# main.net
KiCad netlist of a schematic drawn in Altium Designer
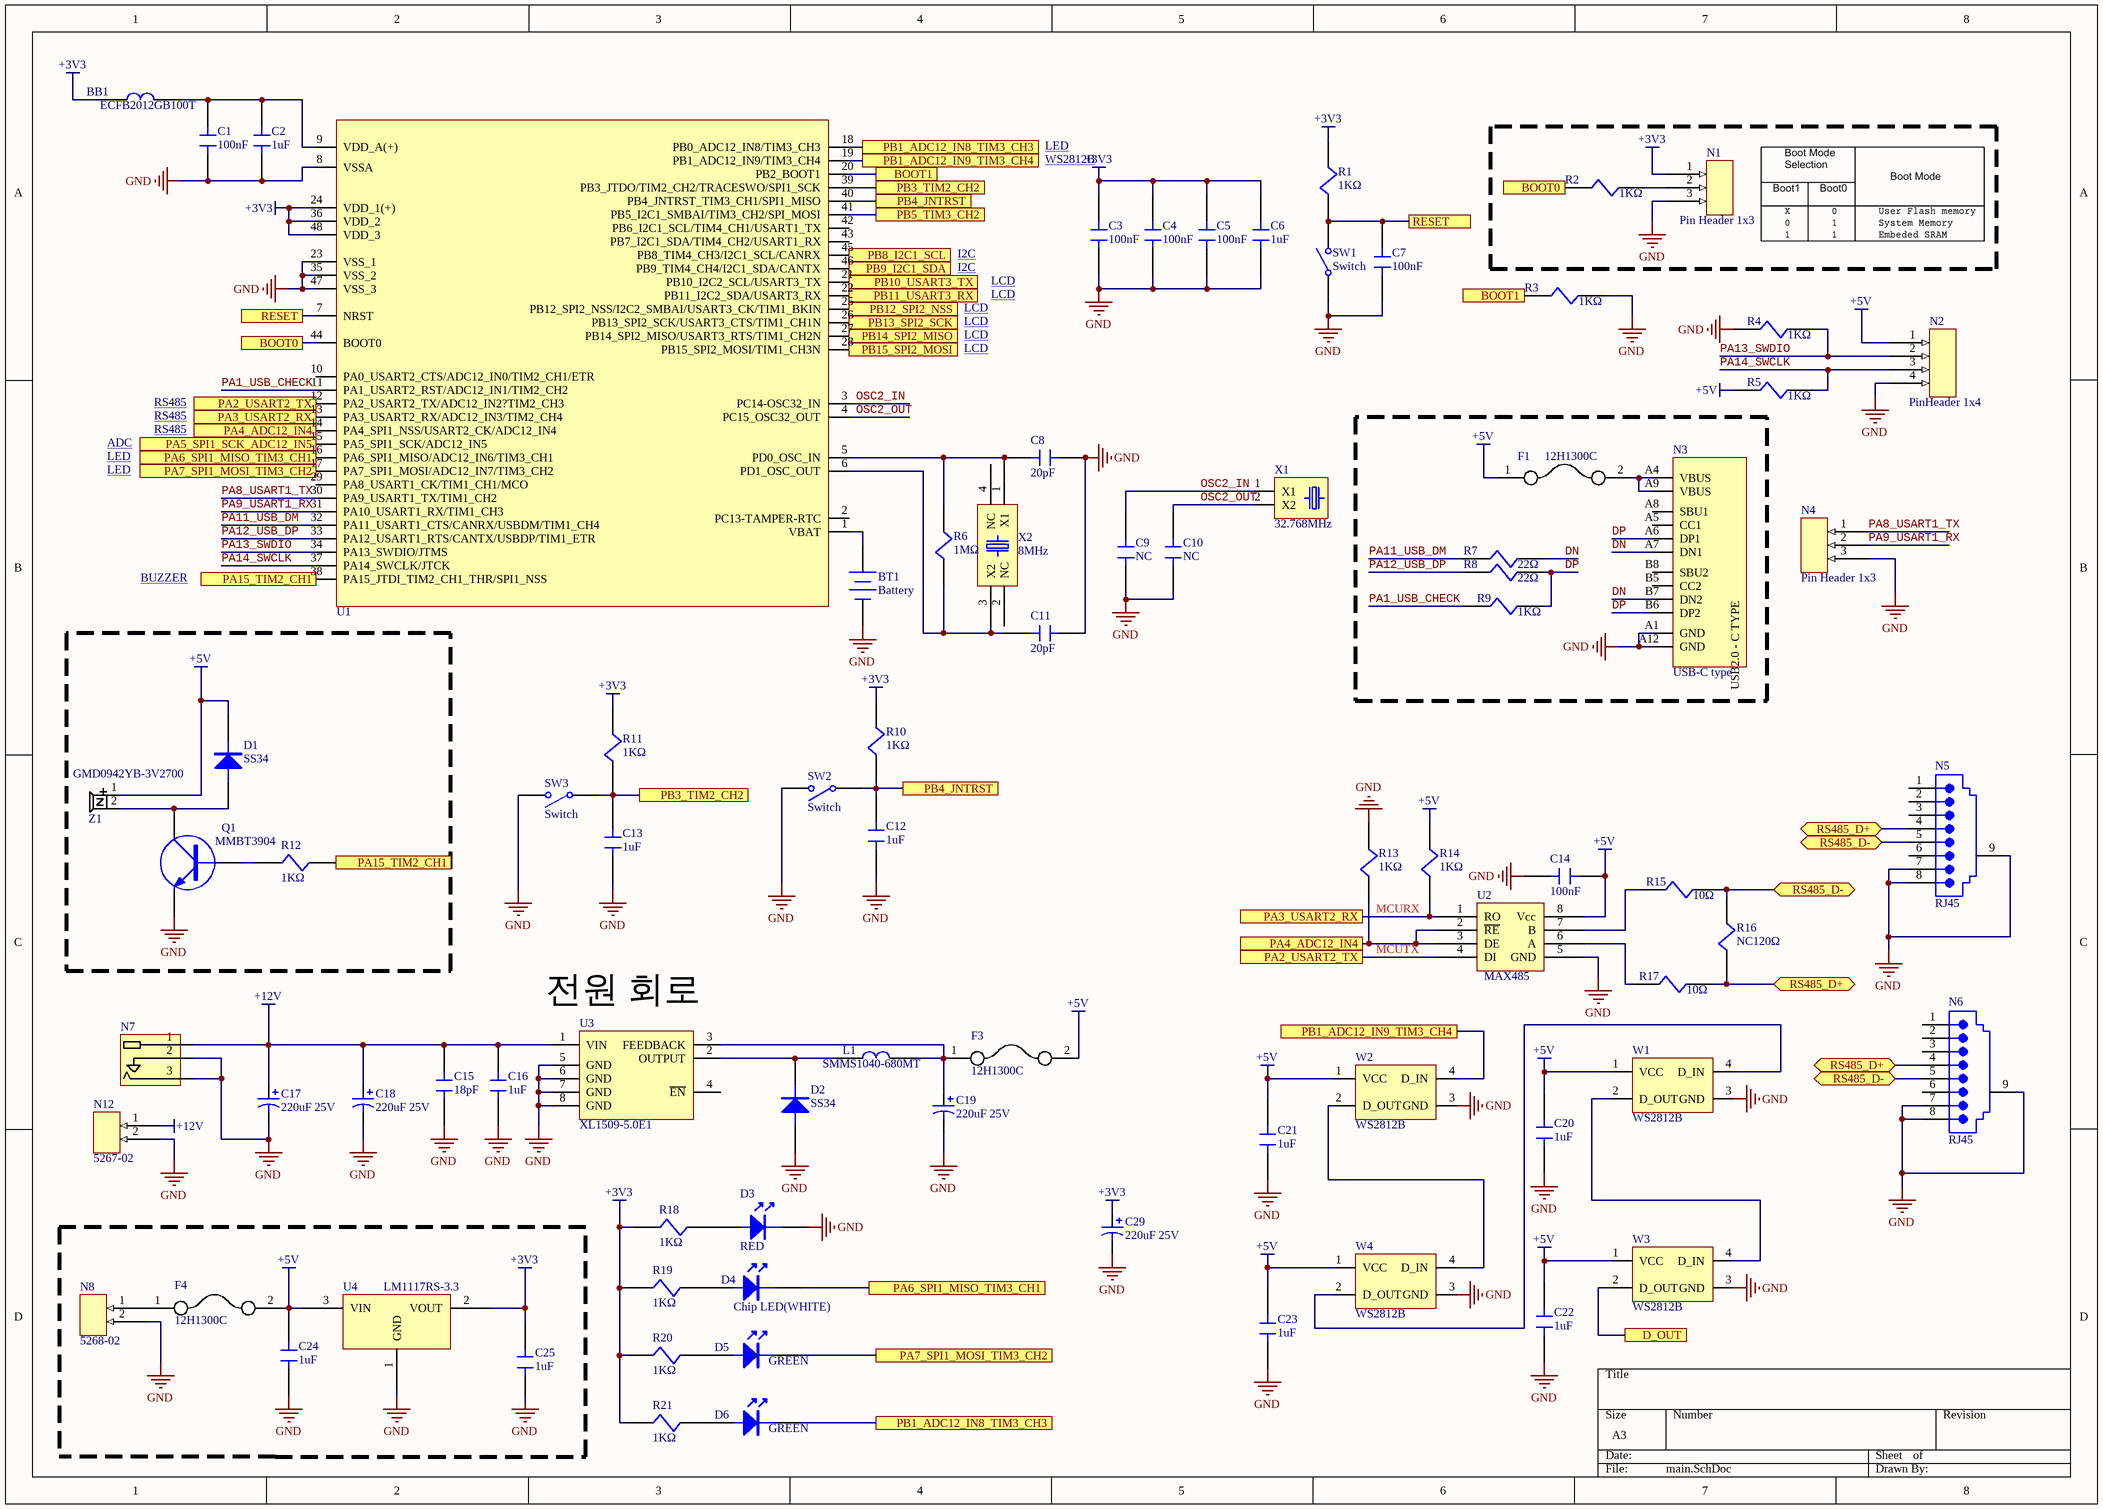
[diagram p0: main.SchDoc]

(export (version "E")
  (design (tool "Eeschema 10.0.6"))
  (components
    (comp (ref "BB1")
      (value "BEAD")
      (footprint "2012-L")
      (description "2012 type Bead")
      (fields (field (name "PART NUMBER") "ECFB2012GB100T"))
      (libsource (lib "SCH_LIB") (part "IND1"))
    )
    (comp (ref "BT1")
      (value "Battery")
      (footprint "CR2032_SMD")
      (description "Multicell Battery")
      (fields (field (name "PUBLISHER") "Altium Limited"))
      (libsource (lib "Miscellaneous Devices") (part "Battery"))
    )
    (comp (ref "C1")
      (value "Chip Capacitor")
      (footprint "1608-C")
      (description "Capacitor, 1608 type")
      (fields (field (name "PART NUMBER") "100nF"))
      (libsource (lib "*") (part "CAP"))
    )
    (comp (ref "C2")
      (value "Chip Capacitor")
      (footprint "1608-C")
      (description "Capacitor, 1608 type")
      (fields (field (name "PART NUMBER") "1uF"))
      (libsource (lib "*") (part "CAP"))
    )
    (comp (ref "C3")
      (value "Chip Capacitor")
      (footprint "1608-C")
      (description "Capacitor, 1608 type")
      (fields (field (name "PART NUMBER") "100nF"))
      (libsource (lib "*") (part "CAP"))
    )
    (comp (ref "C4")
      (value "Chip Capacitor")
      (footprint "1608-C")
      (description "Capacitor, 1608 type")
      (fields (field (name "PART NUMBER") "100nF"))
      (libsource (lib "*") (part "CAP"))
    )
    (comp (ref "C5")
      (value "Chip Capacitor")
      (footprint "1608-C")
      (description "Capacitor, 1608 type")
      (fields (field (name "PART NUMBER") "100nF"))
      (libsource (lib "*") (part "CAP"))
    )
    (comp (ref "C6")
      (value "Chip Capacitor")
      (footprint "1608-C")
      (description "Capacitor, 1608 type")
      (fields (field (name "PART NUMBER") "1uF"))
      (libsource (lib "*") (part "CAP"))
    )
    (comp (ref "C7")
      (value "Chip Capacitor")
      (footprint "1608-C")
      (description "Capacitor, 1608 type")
      (fields (field (name "PART NUMBER") "100nF"))
      (libsource (lib "*") (part "CAP"))
    )
    (comp (ref "C8")
      (value "Chip Capacitor")
      (footprint "1608-C")
      (description "Capacitor, 1608 type")
      (fields (field (name "PART NUMBER") "20pF"))
      (libsource (lib "*") (part "CAP"))
    )
    (comp (ref "C9")
      (value "Chip Capacitor")
      (footprint "1608-C")
      (description "Capacitor, 1608 type")
      (fields (field (name "PART NUMBER") "NC"))
      (libsource (lib "*") (part "CAP"))
    )
    (comp (ref "C10")
      (value "Chip Capacitor")
      (footprint "1608-C")
      (description "Capacitor, 1608 type")
      (fields (field (name "PART NUMBER") "NC"))
      (libsource (lib "*") (part "CAP"))
    )
    (comp (ref "C11")
      (value "Chip Capacitor")
      (footprint "1608-C")
      (description "Capacitor, 1608 type")
      (fields (field (name "PART NUMBER") "20pF"))
      (libsource (lib "*") (part "CAP"))
    )
    (comp (ref "C12")
      (value "Chip Capacitor")
      (footprint "1608-C")
      (description "Capacitor, 1608 type")
      (fields (field (name "PART NUMBER") "1uF"))
      (libsource (lib "*") (part "CAP"))
    )
    (comp (ref "C13")
      (value "Chip Capacitor")
      (footprint "1608-C")
      (description "Capacitor, 1608 type")
      (fields (field (name "PART NUMBER") "1uF"))
      (libsource (lib "*") (part "CAP"))
    )
    (comp (ref "C14")
      (value "Chip Capacitor")
      (footprint "1608-C")
      (description "Capacitor, 1608 type")
      (fields (field (name "PART NUMBER") "100nF"))
      (libsource (lib "*") (part "CAP"))
    )
    (comp (ref "C15")
      (value "Chip Capacitor")
      (footprint "1608-C")
      (description "Capacitor, 1608 type")
      (fields (field (name "PART NUMBER") "18pF"))
      (libsource (lib "*") (part "CAP"))
    )
    (comp (ref "C16")
      (value "Chip Capacitor")
      (footprint "1608-C")
      (description "Capacitor, 1608 type")
      (fields (field (name "PART NUMBER") "1uF"))
      (libsource (lib "*") (part "CAP"))
    )
    (comp (ref "C17")
      (value "Capacitor")
      (footprint "CAP_8X10")
      (description "TanTal Capacitor")
      (fields (field (name "PART NUMBER") "220uF 25V"))
      (libsource (lib "Miscellaneous Devices") (part "Cap Pol1"))
    )
    (comp (ref "C18")
      (value "Capacitor")
      (footprint "CAP_8X10")
      (description "TanTal Capacitor")
      (fields (field (name "PART NUMBER") "220uF 25V"))
      (libsource (lib "Miscellaneous Devices") (part "Cap Pol1"))
    )
    (comp (ref "C19")
      (value "Capacitor")
      (footprint "CAP_8X10")
      (description "TanTal Capacitor")
      (fields (field (name "PART NUMBER") "220uF 25V"))
      (libsource (lib "Miscellaneous Devices") (part "Cap Pol1"))
    )
    (comp (ref "C20")
      (value "Chip Capacitor")
      (footprint "1608-C")
      (description "Capacitor, 1608 type")
      (fields (field (name "PART NUMBER") "1uF"))
      (libsource (lib "*") (part "CAP"))
    )
    (comp (ref "C21")
      (value "Chip Capacitor")
      (footprint "1608-C")
      (description "Capacitor, 1608 type")
      (fields (field (name "PART NUMBER") "1uF"))
      (libsource (lib "*") (part "CAP"))
    )
    (comp (ref "C22")
      (value "Chip Capacitor")
      (footprint "1608-C")
      (description "Capacitor, 1608 type")
      (fields (field (name "PART NUMBER") "1uF"))
      (libsource (lib "*") (part "CAP"))
    )
    (comp (ref "C23")
      (value "Chip Capacitor")
      (footprint "1608-C")
      (description "Capacitor, 1608 type")
      (fields (field (name "PART NUMBER") "1uF"))
      (libsource (lib "*") (part "CAP"))
    )
    (comp (ref "C24")
      (value "Chip Capacitor")
      (footprint "1608-C")
      (description "Capacitor, 1608 type")
      (fields (field (name "PART NUMBER") "1uF"))
      (libsource (lib "*") (part "CAP"))
    )
    (comp (ref "C25")
      (value "Chip Capacitor")
      (footprint "1608-C")
      (description "Capacitor, 1608 type")
      (fields (field (name "PART NUMBER") "1uF"))
      (libsource (lib "*") (part "CAP"))
    )
    (comp (ref "C29")
      (value "Capacitor")
      (footprint "CAP_8X10")
      (description "TanTal Capacitor")
      (fields (field (name "PART NUMBER") "220uF 25V"))
      (libsource (lib "Miscellaneous Devices") (part "Cap Pol1"))
    )
    (comp (ref "D1")
      (value "DIODE")
      (footprint "SS34")
      (fields (field (name "PART NUMBER") "SS34"))
      (libsource (lib "SCH_LIB") (part "DIODE"))
    )
    (comp (ref "D2")
      (value "DIODE")
      (footprint "SS34")
      (fields (field (name "PART NUMBER") "SS34"))
      (libsource (lib "SCH_LIB") (part "DIODE"))
    )
    (comp (ref "D3")
      (value "Chip LED")
      (footprint "1608-LED")
      (description "LED 1608. SMD")
      (fields (field (name "PART NUMBER") "RED"))
      (libsource (lib "SCH_LIB") (part "LED"))
    )
    (comp (ref "D4")
      (value "LED")
      (footprint "1608-LED")
      (description "Green, 1608. SMD")
      (fields (field (name "PART NUMBER") "Chip LED(WHITE)"))
      (libsource (lib "SCH_LIB") (part "LED"))
    )
    (comp (ref "D5")
      (value "Chip LED")
      (footprint "1608-LED")
      (description "LED 1608. SMD")
      (fields (field (name "PART NUMBER") "GREEN"))
      (libsource (lib "SCH_LIB") (part "LED"))
    )
    (comp (ref "D6")
      (value "Chip LED")
      (footprint "1608-LED")
      (description "LED 1608. SMD")
      (fields (field (name "PART NUMBER") "GREEN"))
      (libsource (lib "SCH_LIB") (part "LED"))
    )
    (comp (ref "F1")
      (value "Chip Fuse")
      (footprint "CCP2E30")
      (description "Chip Fuse 3216")
      (fields (field (name "PART NUMBER") "12H1300C"))
      (libsource (lib "SEMIN_LIB_SCH") (part "FUSE_CHIP"))
    )
    (comp (ref "F3")
      (value "Chip Fuse")
      (footprint "CCP2E30")
      (description "Chip Fuse 3216")
      (fields (field (name "PART NUMBER") "12H1300C"))
      (libsource (lib "SEMIN_LIB_SCH") (part "FUSE_CHIP"))
    )
    (comp (ref "F4")
      (value "Chip Fuse")
      (footprint "CCP2E30")
      (description "Chip Fuse 3216")
      (fields (field (name "PART NUMBER") "12H1300C"))
      (libsource (lib "SEMIN_LIB_SCH") (part "FUSE_CHIP"))
    )
    (comp (ref "L1")
      (value "IND1")
      (footprint "inductor_10x40")
      (description "Chip Inductor")
      (fields (field (name "PART NUMBER") "SMMS1040-680MT"))
      (libsource (lib "SCH_LIB") (part "IND1"))
    )
    (comp (ref "N1")
      (value "Connector")
      (footprint "jumper3")
      (description "Pin Header")
      (fields (field (name "PART NUMBER") "Pin Header 1x3"))
      (libsource (lib "SCH_LIB") (part "CON3"))
    )
    (comp (ref "N2")
      (value "Connector")
      (footprint "jumper4")
      (description "Pin Header")
      (fields (field (name "PART NUMBER") "PinHeader 1x4"))
      (libsource (lib "SCH_LIB") (part "CON4"))
    )
    (comp (ref "N3")
      (value "USB-C type")
      (footprint "USB_C_2.0")
      (description "USB2.0-C type")
      (fields (field (name "PART NUMBER") "U262-161N-4BVC11"))
      (libsource (lib "SEMIN_LIB_SCH") (part "USB-C 2.0"))
    )
    (comp (ref "N4")
      (value "Conector")
      (footprint "jumper3")
      (description "Pin Header")
      (fields (field (name "PART NUMBER") "Pin Header 1x3"))
      (libsource (lib "") (part "CON3_1"))
    )
    (comp (ref "N5") (value "RJ45") (footprint "RJ45-PCB830") (libsource (lib "SCH_LIB") (part "RJ45")))
    (comp (ref "N6") (value "RJ45") (footprint "RJ45-PCB830") (libsource (lib "SCH_LIB") (part "RJ45")))
    (comp (ref "N7")
      (value "~")
      (footprint "DC JACK_3.5pi - duplicate")
      (libsource (lib "SEMIN_LIB_SCH") (part "DC_JACK"))
    )
    (comp (ref "N8")
      (value "CONNECTOR")
      (footprint "5268-02")
      (description "Molex")
      (fields (field (name "PART NUMBER") "5268-02"))
      (libsource (lib "SCH_LIB") (part "CON2"))
    )
    (comp (ref "N12")
      (value "CONNECTOR")
      (footprint "5267-02")
      (description "Molex")
      (fields (field (name "PART NUMBER") "5267-02"))
      (libsource (lib "SCH_LIB") (part "CON2"))
    )
    (comp (ref "Q1")
      (value "NPN TR")
      (footprint "SOT-23TR")
      (description "Transistor")
      (fields (field (name "PART NUMBER") "MMBT3904"))
      (libsource (lib "SCH_LIB") (part "TR(NPN)"))
    )
    (comp (ref "R1")
      (value "Chip Resistor")
      (footprint "1608-R")
      (description "Resistor, 1608 type")
      (fields (field (name "PART NUMBER") "1KΩ"))
      (libsource (lib "*") (part "RES1"))
    )
    (comp (ref "R2")
      (value "Chip Resistor")
      (footprint "1608-R")
      (description "Resistor, 1608 type")
      (fields (field (name "PART NUMBER") "1KΩ"))
      (libsource (lib "*") (part "RES1"))
    )
    (comp (ref "R3")
      (value "Chip Resistor")
      (footprint "1608-R")
      (description "Resistor, 1608 type")
      (fields (field (name "PART NUMBER") "1KΩ"))
      (libsource (lib "*") (part "RES1"))
    )
    (comp (ref "R4")
      (value "Chip Resistor")
      (footprint "1608-R")
      (description "Resistor, 1608 type")
      (fields (field (name "PART NUMBER") "1KΩ"))
      (libsource (lib "*") (part "RES1"))
    )
    (comp (ref "R5")
      (value "Chip Resistor")
      (footprint "1608-R")
      (description "Resistor, 1608 type")
      (fields (field (name "PART NUMBER") "1KΩ"))
      (libsource (lib "*") (part "RES1"))
    )
    (comp (ref "R6")
      (value "Chip Resistor")
      (footprint "1608-R")
      (description "Resistor, 1608 type")
      (fields (field (name "PART NUMBER") "1MΩ"))
      (libsource (lib "*") (part "RES1"))
    )
    (comp (ref "R7")
      (value "Chip Resistor")
      (footprint "1608-R")
      (description "Resistor, 1608 type")
      (fields (field (name "PART NUMBER") "22Ω"))
      (libsource (lib "*") (part "RES1"))
    )
    (comp (ref "R8")
      (value "Chip Resistor")
      (footprint "1608-R")
      (description "Resistor, 1608 type")
      (fields (field (name "PART NUMBER") "22Ω"))
      (libsource (lib "*") (part "RES1"))
    )
    (comp (ref "R9")
      (value "Chip Resistor")
      (footprint "1608-R")
      (description "Resistor, 1608 type")
      (fields (field (name "PART NUMBER") "1KΩ"))
      (libsource (lib "*") (part "RES1"))
    )
    (comp (ref "R10")
      (value "Chip Resistor")
      (footprint "1608-R")
      (description "Resistor, 1608 type")
      (fields (field (name "PART NUMBER") "1KΩ"))
      (libsource (lib "*") (part "RES1"))
    )
    (comp (ref "R11")
      (value "Chip Resistor")
      (footprint "1608-R")
      (description "Resistor, 1608 type")
      (fields (field (name "PART NUMBER") "1KΩ"))
      (libsource (lib "*") (part "RES1"))
    )
    (comp (ref "R12")
      (value "Chip Resistor")
      (footprint "1608-R")
      (description "Resistor, 1608 type")
      (fields (field (name "PART NUMBER") "1KΩ"))
      (libsource (lib "*") (part "RES1"))
    )
    (comp (ref "R13")
      (value "Chip Resistor")
      (footprint "1608-R")
      (description "Resistor, 1608 type")
      (fields (field (name "PART NUMBER") "1KΩ"))
      (libsource (lib "*") (part "RES1"))
    )
    (comp (ref "R14")
      (value "Chip Resistor")
      (footprint "1608-R")
      (description "Resistor, 1608 type")
      (fields (field (name "PART NUMBER") "1KΩ"))
      (libsource (lib "*") (part "RES1"))
    )
    (comp (ref "R15")
      (value "Chip Resistor")
      (footprint "1608-R")
      (description "Resistor, 1608 type")
      (fields (field (name "PART NUMBER") "10Ω"))
      (libsource (lib "*") (part "RES1"))
    )
    (comp (ref "R16")
      (value "Chip Resistor")
      (footprint "1608-R")
      (description "Resistor, 1608 type")
      (fields (field (name "PART NUMBER") "NC120Ω"))
      (libsource (lib "*") (part "RES1"))
    )
    (comp (ref "R17")
      (value "Chip Resistor")
      (footprint "1608-R")
      (description "Resistor, 1608 type")
      (fields (field (name "PART NUMBER") "10Ω"))
      (libsource (lib "*") (part "RES1"))
    )
    (comp (ref "R18")
      (value "Chip Resistor")
      (footprint "1608-R")
      (description "Resistor, 1608 type")
      (fields (field (name "PART NUMBER") "1KΩ"))
      (libsource (lib "*") (part "RES1"))
    )
    (comp (ref "R19")
      (value "Chip Resistor")
      (footprint "1608-R")
      (description "Resistor, 1608 type")
      (fields (field (name "PART NUMBER") "1KΩ"))
      (libsource (lib "*") (part "RES1"))
    )
    (comp (ref "R20")
      (value "Chip Resistor")
      (footprint "1608-R")
      (description "Resistor, 1608 type")
      (fields (field (name "PART NUMBER") "1KΩ"))
      (libsource (lib "*") (part "RES1"))
    )
    (comp (ref "R21")
      (value "Chip Resistor")
      (footprint "1608-R")
      (description "Resistor, 1608 type")
      (fields (field (name "PART NUMBER") "1KΩ"))
      (libsource (lib "*") (part "RES1"))
    )
    (comp (ref "SW1")
      (value "Switch")
      (footprint "TACT_Micro")
      (description "Single-Pole, Single-Throw Switch")
      (fields (field (name "PUBLISHER") "Altium Limited"))
      (libsource (lib "Miscellaneous Devices") (part "SW-SPST"))
    )
    (comp (ref "SW2")
      (value "Switch")
      (footprint "TACT_Micro")
      (description "Single-Pole, Single-Throw Switch")
      (fields (field (name "PUBLISHER") "Altium Limited"))
      (libsource (lib "Miscellaneous Devices") (part "SW-SPST"))
    )
    (comp (ref "SW3")
      (value "Switch")
      (footprint "TACT_Micro")
      (description "Single-Pole, Single-Throw Switch")
      (fields (field (name "PUBLISHER") "Altium Limited"))
      (libsource (lib "Miscellaneous Devices") (part "SW-SPST"))
    )
    (comp (ref "U1")
      (value "MCU")
      (footprint "LQFP-48")
      (description "ARM-based 32bit MCU")
      (libsource (lib "SCH_LIB") (part "STM32F103_LQFP64"))
    )
    (comp (ref "U2")
      (value "Driver")
      (footprint "SO-8")
      (description "RS485 Driver")
      (fields (field (name "PART NUMBER") "MAX485"))
      (libsource (lib "SCH_LIB") (part "MAX485-SO8"))
    )
    (comp (ref "U3")
      (value "Buck Converter")
      (footprint "SOIC-8")
      (description "2A 150KHz 40V Buck DC to DC Converter")
      (fields (field (name "PART NUMBER") "XL1509-5.0E1"))
      (libsource (lib "SEMIN_LIB_SCH") (part "XL1509_FIX"))
    )
    (comp (ref "U4")
      (value "Regulator")
      (footprint "D-PAK_TO252")
      (description "LM1117-3.3 / 3.3V OUT / MAX 1A")
      (fields (field (name "PART NUMBER") "LM1117RS-3.3"))
      (libsource (lib "SEMIN_LIB_SCH") (part "7803(SOT-223)"))
    )
    (comp (ref "W1")
      (value "LED")
      (footprint "semin_PCB_LIB_1:WS2812B _Mini")
      (description "DC 5V / 60mA WS2812B")
      (fields (field (name "PART NUMBER") "WS2812B"))
      (libsource (lib "SEMIN_LIB_SCH") (part "WS2812B"))
    )
    (comp (ref "W2")
      (value "LED")
      (footprint "semin_PCB_LIB_1:WS2812B _Mini")
      (description "DC 5V / 60mA WS2812B")
      (fields (field (name "PART NUMBER") "WS2812B"))
      (libsource (lib "SEMIN_LIB_SCH") (part "WS2812B"))
    )
    (comp (ref "W3")
      (value "LED")
      (footprint "semin_PCB_LIB_1:WS2812B _Mini")
      (description "DC 5V / 60mA WS2812B")
      (fields (field (name "PART NUMBER") "WS2812B"))
      (libsource (lib "SEMIN_LIB_SCH") (part "WS2812B"))
    )
    (comp (ref "W4")
      (value "LED")
      (footprint "semin_PCB_LIB_1:WS2812B _Mini")
      (description "DC 5V / 60mA WS2812B")
      (fields (field (name "PART NUMBER") "WS2812B"))
      (libsource (lib "SEMIN_LIB_SCH") (part "WS2812B"))
    )
    (comp (ref "X1")
      (value "32.768MHz")
      (footprint "XTAL_2012")
      (description "Crystal")
      (fields (field (name "PART NUMBER") "Q13FC1350000400"))
      (libsource (lib "SCH_LIB") (part "XTAL_2"))
    )
    (comp (ref "X2")
      (value "CRYSTAL")
      (footprint "XTAL3225")
      (description "8MHz  3X5 CERAMIC SMD CRYSTAL")
      (fields (field (name "PART NUMBER") "8MHz"))
      (libsource (lib "SCH_LIB") (part "XTAL_5"))
    )
    (comp (ref "Z1")
      (value "GMD0942YB-3V2700")
      (footprint "Buzzer_9mm")
      (description "피에조 부저")
      (libsource (lib "SEMIN_LIB_SCH") (part "BUZZER"))
    )
  )
  (nets
    (net (code "1") (name "+3V3") (class "Default")
      (node (ref "BB1") (pin "1") (pintype "passive"))
      (node (ref "C25") (pin "2") (pinfunction "2_2") (pintype "passive"))
      (node (ref "C29") (pin "1") (pinfunction "1_1") (pintype "passive"))
      (node (ref "C3") (pin "1") (pinfunction "1_1") (pintype "passive"))
      (node (ref "C4") (pin "1") (pinfunction "1_1") (pintype "passive"))
      (node (ref "C5") (pin "1") (pinfunction "1_1") (pintype "passive"))
      (node (ref "C6") (pin "2") (pinfunction "2_2") (pintype "passive"))
      (node (ref "N1") (pin "1") (pintype "input"))
      (node (ref "R1") (pin "1") (pinfunction "1_1") (pintype "passive"))
      (node (ref "R10") (pin "2") (pinfunction "2_2") (pintype "passive"))
      (node (ref "R11") (pin "2") (pinfunction "2_2") (pintype "passive"))
      (node (ref "R18") (pin "2") (pinfunction "2_2") (pintype "passive"))
      (node (ref "R19") (pin "2") (pinfunction "2_2") (pintype "passive"))
      (node (ref "R20") (pin "2") (pinfunction "2_2") (pintype "passive"))
      (node (ref "R21") (pin "2") (pinfunction "2_2") (pintype "passive"))
      (node (ref "U1") (pin "24") (pinfunction "VDD_1(+)_24") (pintype "passive"))
      (node (ref "U1") (pin "36") (pinfunction "VDD_2_36") (pintype "passive"))
      (node (ref "U1") (pin "48") (pinfunction "VDD_3_48") (pintype "passive"))
      (node (ref "U4") (pin "2") (pinfunction "VOUT_2") (pintype "passive"))
    )
    (net (code "2") (name "+5V") (class "Default")
      (node (ref "C14") (pin "1") (pinfunction "1_1") (pintype "passive"))
      (node (ref "C20") (pin "2") (pinfunction "2_2") (pintype "passive"))
      (node (ref "C21") (pin "2") (pinfunction "2_2") (pintype "passive"))
      (node (ref "C22") (pin "2") (pinfunction "2_2") (pintype "passive"))
      (node (ref "C23") (pin "2") (pinfunction "2_2") (pintype "passive"))
      (node (ref "C24") (pin "2") (pinfunction "2_2") (pintype "passive"))
      (node (ref "D1") (pin "2") (pinfunction "K_2") (pintype "passive"))
      (node (ref "F1") (pin "1") (pinfunction "6_1") (pintype "passive"))
      (node (ref "F3") (pin "2") (pinfunction "7_2") (pintype "passive"))
      (node (ref "F4") (pin "2") (pinfunction "7_2") (pintype "passive"))
      (node (ref "N2") (pin "1") (pintype "input"))
      (node (ref "R14") (pin "2") (pinfunction "2_2") (pintype "passive"))
      (node (ref "R5") (pin "1") (pinfunction "1_1") (pintype "passive"))
      (node (ref "U2") (pin "8") (pinfunction "Vcc_8") (pintype "passive"))
      (node (ref "U4") (pin "3") (pinfunction "VIN_3") (pintype "passive"))
      (node (ref "W1") (pin "1") (pinfunction "VCC_1") (pintype "passive"))
      (node (ref "W2") (pin "1") (pinfunction "VCC_1") (pintype "passive"))
      (node (ref "W3") (pin "1") (pinfunction "VCC_1") (pintype "passive"))
      (node (ref "W4") (pin "1") (pinfunction "VCC_1") (pintype "passive"))
      (node (ref "Z1") (pin "1") (pinfunction "VCC_1") (pintype "passive"))
    )
    (net (code "3") (name "+12V") (class "Default")
      (node (ref "C15") (pin "2") (pinfunction "2_2") (pintype "passive"))
      (node (ref "C16") (pin "2") (pinfunction "2_2") (pintype "passive"))
      (node (ref "C17") (pin "1") (pinfunction "1_1") (pintype "passive"))
      (node (ref "C18") (pin "1") (pinfunction "1_1") (pintype "passive"))
      (node (ref "N12") (pin "1") (pintype "input"))
      (node (ref "N7") (pin "1") (pinfunction "1_1") (pintype "passive"))
      (node (ref "U3") (pin "1") (pinfunction "VIN_1") (pintype "passive"))
    )
    (net (code "4") (name "/BOOT0") (class "Default")
      (node (ref "R2") (pin "2") (pinfunction "2_2") (pintype "passive"))
      (node (ref "U1") (pin "44") (pinfunction "BOOT0_44") (pintype "passive"))
    )
    (net (code "5") (name "/BOOT1") (class "Default")
      (node (ref "R3") (pin "2") (pinfunction "2_2") (pintype "passive"))
      (node (ref "U1") (pin "20") (pinfunction "PB2_BOOT1_20") (pintype "passive"))
    )
    (net (code "6") (name "/DN") (class "Default")
      (node (ref "N3") (pin "A7") (pinfunction "DN1_A7") (pintype "passive"))
      (node (ref "N3") (pin "B7") (pinfunction "DN2_B7") (pintype "passive"))
      (node (ref "R7") (pin "1") (pinfunction "1_1") (pintype "passive"))
    )
    (net (code "7") (name "/DP") (class "Default")
      (node (ref "N3") (pin "A6") (pinfunction "DP1_A6") (pintype "passive"))
      (node (ref "N3") (pin "B6") (pinfunction "DP2_B6") (pintype "passive"))
      (node (ref "R8") (pin "1") (pinfunction "1_1") (pintype "passive"))
      (node (ref "R9") (pin "2") (pinfunction "2_2") (pintype "passive"))
    )
    (net (code "8") (name "/D_OUT") (class "Default")
      (node (ref "W3") (pin "2") (pinfunction "D_OUT_2") (pintype "passive"))
    )
    (net (code "9") (name "/OSC2_IN") (class "Default")
      (node (ref "C9") (pin "2") (pinfunction "2_2") (pintype "passive"))
      (node (ref "U1") (pin "3") (pinfunction "PC14-OSC32_IN_3") (pintype "passive"))
      (node (ref "X1") (pin "1") (pinfunction "X1_1") (pintype "passive"))
    )
    (net (code "10") (name "/OSC2_OUT") (class "Default")
      (node (ref "C10") (pin "2") (pinfunction "2_2") (pintype "passive"))
      (node (ref "U1") (pin "4") (pinfunction "PC15_OSC32_OUT_4") (pintype "passive"))
      (node (ref "X1") (pin "2") (pinfunction "X2_2") (pintype "passive"))
    )
    (net (code "11") (name "/PA1_USB_CHECK") (class "Default")
      (node (ref "R9") (pin "1") (pinfunction "1_1") (pintype "passive"))
      (node (ref "U1") (pin "11") (pinfunction "PA1_USART2_RST/ADC12_IN1/TIM2_CH2_11") (pintype "passive"))
    )
    (net (code "12") (name "/PA2_USART2_TX") (class "Default")
      (node (ref "U1") (pin "12") (pinfunction "PA2_USART2_TX/ADC12_IN2?TIM2_CH3_12") (pintype "passive"))
      (node (ref "U2") (pin "4") (pinfunction "DI_4") (pintype "passive"))
    )
    (net (code "13") (name "/PA3_USART2_RX") (class "Default")
      (node (ref "R14") (pin "1") (pinfunction "1_1") (pintype "passive"))
      (node (ref "U1") (pin "13") (pinfunction "PA3_USART2_RX/ADC12_IN3/TIM2_CH4_13") (pintype "passive"))
      (node (ref "U2") (pin "1") (pinfunction "RO_1") (pintype "passive"))
    )
    (net (code "14") (name "/PA4_ADC12_IN4") (class "Default")
      (node (ref "R13") (pin "1") (pinfunction "1_1") (pintype "passive"))
      (node (ref "U1") (pin "14") (pinfunction "PA4_SPI1_NSS/USART2_CK/ADC12_IN4_14") (pintype "passive"))
      (node (ref "U2") (pin "2") (pinfunction "~{RE}_2") (pintype "passive"))
      (node (ref "U2") (pin "3") (pinfunction "DE_3") (pintype "passive"))
    )
    (net (code "15") (name "/PA5_SPI1_SCK_ADC12_IN5") (class "Default")
      (node (ref "U1") (pin "15") (pinfunction "PA5_SPI1_SCK/ADC12_IN5_15") (pintype "passive"))
    )
    (net (code "16") (name "/PA6_SPI1_MISO_TIM3_CH1") (class "Default")
      (node (ref "D4") (pin "2") (pinfunction "2_2") (pintype "passive"))
      (node (ref "U1") (pin "16") (pinfunction "PA6_SPI1_MISO/ADC12_IN6/TIM3_CH1_16") (pintype "passive"))
    )
    (net (code "17") (name "/PA7_SPI1_MOSI_TIM3_CH2") (class "Default")
      (node (ref "D5") (pin "2") (pinfunction "2_2") (pintype "passive"))
      (node (ref "U1") (pin "17") (pinfunction "PA7_SPI1_MOSI/ADC12_IN7/TIM3_CH2_17") (pintype "passive"))
    )
    (net (code "18") (name "/PA8_USART1_TX") (class "Default")
      (node (ref "N4") (pin "1") (pintype "input"))
      (node (ref "U1") (pin "30") (pinfunction "PA9_USART1_TX/TIM1_CH2_30") (pintype "passive"))
    )
    (net (code "19") (name "/PA9_USART1_RX") (class "Default")
      (node (ref "N4") (pin "2") (pintype "input"))
      (node (ref "U1") (pin "31") (pinfunction "PA10_USART1_RX/TIM1_CH3_31") (pintype "passive"))
    )
    (net (code "20") (name "/PA11_USB_DM") (class "Default")
      (node (ref "R7") (pin "2") (pinfunction "2_2") (pintype "passive"))
      (node (ref "U1") (pin "32") (pinfunction "PA11_USART1_CTS/CANRX/USBDM/TIM1_CH4_32") (pintype "passive"))
    )
    (net (code "21") (name "/PA12_USB_DP") (class "Default")
      (node (ref "R8") (pin "2") (pinfunction "2_2") (pintype "passive"))
      (node (ref "U1") (pin "33") (pinfunction "PA12_USART1_RTS/CANTX/USBDP/TIM1_ETR_33") (pintype "passive"))
    )
    (net (code "22") (name "/PA13_SWDIO") (class "Default")
      (node (ref "N2") (pin "2") (pintype "input"))
      (node (ref "R4") (pin "2") (pinfunction "2_2") (pintype "passive"))
      (node (ref "U1") (pin "34") (pinfunction "PA13_SWDIO/JTMS_34") (pintype "passive"))
    )
    (net (code "23") (name "/PA14_SWCLK") (class "Default")
      (node (ref "N2") (pin "3") (pintype "input"))
      (node (ref "R5") (pin "2") (pinfunction "2_2") (pintype "passive"))
      (node (ref "U1") (pin "37") (pinfunction "PA14_SWCLK/JTCK_37") (pintype "passive"))
    )
    (net (code "24") (name "/PA15_TIM2_CH1") (class "Default")
      (node (ref "R12") (pin "1") (pinfunction "1_1") (pintype "passive"))
      (node (ref "U1") (pin "38") (pinfunction "PA15_JTDI_TIM2_CH1_THR/SPI1_NSS_38") (pintype "passive"))
    )
    (net (code "25") (name "/PB1_ADC12_IN8_TIM3_CH3") (class "Default")
      (node (ref "D6") (pin "2") (pinfunction "2_2") (pintype "passive"))
      (node (ref "U1") (pin "18") (pinfunction "PB0_ADC12_IN8/TIM3_CH3_18") (pintype "passive"))
    )
    (net (code "26") (name "/PB1_ADC12_IN9_TIM3_CH4") (class "Default")
      (node (ref "U1") (pin "19") (pinfunction "PB1_ADC12_IN9/TIM3_CH4_19") (pintype "passive"))
      (node (ref "W2") (pin "4") (pinfunction "D_IN_4") (pintype "passive"))
    )
    (net (code "27") (name "/PB3_TIM2_CH2") (class "Default")
      (node (ref "C13") (pin "1") (pinfunction "1_1") (pintype "passive"))
      (node (ref "R11") (pin "1") (pinfunction "1_1") (pintype "passive"))
      (node (ref "SW3") (pin "1") (pinfunction "COMMON_1") (pintype "passive"))
      (node (ref "U1") (pin "39") (pinfunction "PB3_JTDO/TIM2_CH2/TRACESWO/SPI1_SCK_39") (pintype "passive"))
    )
    (net (code "28") (name "/PB4_JNTRST") (class "Default")
      (node (ref "C12") (pin "1") (pinfunction "1_1") (pintype "passive"))
      (node (ref "R10") (pin "1") (pinfunction "1_1") (pintype "passive"))
      (node (ref "SW2") (pin "1") (pinfunction "COMMON_1") (pintype "passive"))
      (node (ref "U1") (pin "40") (pinfunction "PB4_JNTRST_TIM3_CH1/SPI1_MISO_40") (pintype "passive"))
    )
    (net (code "29") (name "/PB5_TIM3_CH2") (class "Default")
      (node (ref "U1") (pin "41") (pinfunction "PB5_I2C1_SMBAI/TIM3_CH2/SPI_MOSI_41") (pintype "passive"))
    )
    (net (code "30") (name "/PB8_I2C1_SCL") (class "Default")
      (node (ref "U1") (pin "45") (pinfunction "PB8_TIM4_CH3/I2C1_SCL/CANRX_45") (pintype "passive"))
    )
    (net (code "31") (name "/PB9_I2C1_SDA") (class "Default")
      (node (ref "U1") (pin "46") (pinfunction "PB9_TIM4_CH4/I2C1_SDA/CANTX_46") (pintype "passive"))
    )
    (net (code "32") (name "/PB10_USART3_TX") (class "Default")
      (node (ref "U1") (pin "21") (pinfunction "PB10_I2C2_SCL/USART3_TX_21") (pintype "passive"))
    )
    (net (code "33") (name "/PB11_USART3_RX") (class "Default")
      (node (ref "U1") (pin "22") (pinfunction "PB11_I2C2_SDA/USART3_RX_22") (pintype "passive"))
    )
    (net (code "34") (name "/PB12_SPI2_NSS") (class "Default")
      (node (ref "U1") (pin "25") (pinfunction "PB12_SPI2_NSS/I2C2_SMBAI/USART3_CK/TIM1_BKIN_25") (pintype "passive"))
    )
    (net (code "35") (name "/PB13_SPI2_SCK") (class "Default")
      (node (ref "U1") (pin "26") (pinfunction "PB13_SPI2_SCK/USART3_CTS/TIM1_CH1N_26") (pintype "passive"))
    )
    (net (code "36") (name "/PB14_SPI2_MISO") (class "Default")
      (node (ref "U1") (pin "27") (pinfunction "PB14_SPI2_MISO/USART3_RTS/TIM1_CH2N_27") (pintype "passive"))
    )
    (net (code "37") (name "/PB15_SPI2_MOSI") (class "Default")
      (node (ref "U1") (pin "28") (pinfunction "PB15_SPI2_MOSI/TIM1_CH3N_28") (pintype "passive"))
    )
    (net (code "38") (name "/RESET") (class "Default")
      (node (ref "C7") (pin "1") (pinfunction "1_1") (pintype "passive"))
      (node (ref "R1") (pin "2") (pinfunction "2_2") (pintype "passive"))
      (node (ref "SW1") (pin "2") (pinfunction "NO_2") (pintype "passive"))
      (node (ref "U1") (pin "7") (pinfunction "NRST_7") (pintype "passive"))
    )
    (net (code "39") (name "/RS485_D+") (class "Default")
      (node (ref "N5") (pin "4") (pinfunction "4_4") (pintype "passive"))
      (node (ref "N6") (pin "4") (pinfunction "4_4") (pintype "passive"))
      (node (ref "R16") (pin "1") (pinfunction "1_1") (pintype "passive"))
      (node (ref "R17") (pin "2") (pinfunction "2_2") (pintype "passive"))
    )
    (net (code "40") (name "/RS485_D-") (class "Default")
      (node (ref "N5") (pin "5") (pinfunction "5_5") (pintype "passive"))
      (node (ref "N6") (pin "5") (pinfunction "5_5") (pintype "passive"))
      (node (ref "R15") (pin "2") (pinfunction "2_2") (pintype "passive"))
      (node (ref "R16") (pin "2") (pinfunction "2_2") (pintype "passive"))
    )
    (net (code "41") (name "GND") (class "Default")
      (node (ref "BT1") (pin "2") (pinfunction "-_2") (pintype "passive"))
      (node (ref "C1") (pin "2") (pinfunction "2_2") (pintype "passive"))
      (node (ref "C10") (pin "1") (pinfunction "1_1") (pintype "passive"))
      (node (ref "C11") (pin "2") (pinfunction "2_2") (pintype "passive"))
      (node (ref "C12") (pin "2") (pinfunction "2_2") (pintype "passive"))
      (node (ref "C13") (pin "2") (pinfunction "2_2") (pintype "passive"))
      (node (ref "C14") (pin "2") (pinfunction "2_2") (pintype "passive"))
      (node (ref "C15") (pin "1") (pinfunction "1_1") (pintype "passive"))
      (node (ref "C16") (pin "1") (pinfunction "1_1") (pintype "passive"))
      (node (ref "C17") (pin "2") (pinfunction "2_2") (pintype "passive"))
      (node (ref "C18") (pin "2") (pinfunction "2_2") (pintype "passive"))
      (node (ref "C19") (pin "2") (pinfunction "2_2") (pintype "passive"))
      (node (ref "C2") (pin "1") (pinfunction "1_1") (pintype "passive"))
      (node (ref "C20") (pin "1") (pinfunction "1_1") (pintype "passive"))
      (node (ref "C21") (pin "1") (pinfunction "1_1") (pintype "passive"))
      (node (ref "C22") (pin "1") (pinfunction "1_1") (pintype "passive"))
      (node (ref "C23") (pin "1") (pinfunction "1_1") (pintype "passive"))
      (node (ref "C24") (pin "1") (pinfunction "1_1") (pintype "passive"))
      (node (ref "C25") (pin "1") (pinfunction "1_1") (pintype "passive"))
      (node (ref "C29") (pin "2") (pinfunction "2_2") (pintype "passive"))
      (node (ref "C3") (pin "2") (pinfunction "2_2") (pintype "passive"))
      (node (ref "C4") (pin "2") (pinfunction "2_2") (pintype "passive"))
      (node (ref "C5") (pin "2") (pinfunction "2_2") (pintype "passive"))
      (node (ref "C6") (pin "1") (pinfunction "1_1") (pintype "passive"))
      (node (ref "C7") (pin "2") (pinfunction "2_2") (pintype "passive"))
      (node (ref "C8") (pin "2") (pinfunction "2_2") (pintype "passive"))
      (node (ref "C9") (pin "1") (pinfunction "1_1") (pintype "passive"))
      (node (ref "D2") (pin "1") (pinfunction "A_1") (pintype "passive"))
      (node (ref "D3") (pin "2") (pinfunction "2_2") (pintype "passive"))
      (node (ref "N1") (pin "3") (pintype "input"))
      (node (ref "N12") (pin "2") (pintype "input"))
      (node (ref "N2") (pin "4") (pintype "input"))
      (node (ref "N3") (pin "A1") (pinfunction "GND_A1") (pintype "passive"))
      (node (ref "N3") (pin "A12") (pinfunction "GND_A12") (pintype "passive"))
      (node (ref "N4") (pin "3") (pintype "input"))
      (node (ref "N5") (pin "7") (pinfunction "7_7") (pintype "passive"))
      (node (ref "N5") (pin "8") (pinfunction "8_8") (pintype "passive"))
      (node (ref "N5") (pin "9") (pinfunction "G_9") (pintype "passive"))
      (node (ref "N6") (pin "7") (pinfunction "7_7") (pintype "passive"))
      (node (ref "N6") (pin "8") (pinfunction "8_8") (pintype "passive"))
      (node (ref "N6") (pin "9") (pinfunction "G_9") (pintype "passive"))
      (node (ref "N7") (pin "2") (pinfunction "2_2") (pintype "passive"))
      (node (ref "N7") (pin "3") (pinfunction "3_3") (pintype "passive"))
      (node (ref "N8") (pin "2") (pintype "input"))
      (node (ref "Q1") (pin "3") (pinfunction "E_3") (pintype "passive"))
      (node (ref "R13") (pin "2") (pinfunction "2_2") (pintype "passive"))
      (node (ref "R3") (pin "1") (pinfunction "1_1") (pintype "passive"))
      (node (ref "R4") (pin "1") (pinfunction "1_1") (pintype "passive"))
      (node (ref "SW1") (pin "1") (pinfunction "COMMON_1") (pintype "passive"))
      (node (ref "SW2") (pin "2") (pinfunction "NO_2") (pintype "passive"))
      (node (ref "SW3") (pin "2") (pinfunction "NO_2") (pintype "passive"))
      (node (ref "U1") (pin "23") (pinfunction "VSS_1_23") (pintype "passive"))
      (node (ref "U1") (pin "35") (pinfunction "VSS_2_35") (pintype "passive"))
      (node (ref "U1") (pin "47") (pinfunction "VSS_3_47") (pintype "passive"))
      (node (ref "U1") (pin "8") (pinfunction "VSSA_8") (pintype "passive"))
      (node (ref "U2") (pin "5") (pinfunction "GND_5") (pintype "passive"))
      (node (ref "U3") (pin "5") (pinfunction "GND_5") (pintype "passive"))
      (node (ref "U3") (pin "6") (pinfunction "GND_6") (pintype "passive"))
      (node (ref "U3") (pin "7") (pinfunction "GND_7") (pintype "passive"))
      (node (ref "U3") (pin "8") (pinfunction "GND_8") (pintype "passive"))
      (node (ref "U4") (pin "1") (pinfunction "GND_1") (pintype "passive"))
      (node (ref "W1") (pin "3") (pinfunction "GND_3") (pintype "passive"))
      (node (ref "W2") (pin "3") (pinfunction "GND_3") (pintype "passive"))
      (node (ref "W3") (pin "3") (pinfunction "GND_3") (pintype "passive"))
      (node (ref "W4") (pin "3") (pinfunction "GND_3") (pintype "passive"))
    )
    (net (code "42") (name "Net-(BT1-+)") (class "Default")
      (node (ref "BT1") (pin "1") (pinfunction "+_1") (pintype "passive"))
      (node (ref "U1") (pin "1") (pinfunction "VBAT_1") (pintype "passive"))
    )
    (net (code "43") (name "Net-(D1-A)") (class "Default")
      (node (ref "D1") (pin "1") (pinfunction "A_1") (pintype "passive"))
      (node (ref "Q1") (pin "2") (pinfunction "C_2") (pintype "passive"))
      (node (ref "Z1") (pin "2") (pinfunction "VCC_2") (pintype "passive"))
    )
    (net (code "44") (name "Net-(D2-K)") (class "Default")
      (node (ref "D2") (pin "2") (pinfunction "K_2") (pintype "passive"))
      (node (ref "L1") (pin "1") (pintype "passive"))
      (node (ref "U3") (pin "2") (pinfunction "OUTPUT_2") (pintype "passive"))
    )
    (net (code "45") (name "Net-(D3-Pad1)") (class "Default")
      (node (ref "D3") (pin "1") (pinfunction "1_1") (pintype "passive"))
      (node (ref "R18") (pin "1") (pinfunction "1_1") (pintype "passive"))
    )
    (net (code "46") (name "Net-(D4-Pad1)") (class "Default")
      (node (ref "D4") (pin "1") (pinfunction "1_1") (pintype "passive"))
      (node (ref "R19") (pin "1") (pinfunction "1_1") (pintype "passive"))
    )
    (net (code "47") (name "Net-(D5-Pad1)") (class "Default")
      (node (ref "D5") (pin "1") (pinfunction "1_1") (pintype "passive"))
      (node (ref "R20") (pin "1") (pinfunction "1_1") (pintype "passive"))
    )
    (net (code "48") (name "Net-(D6-Pad1)") (class "Default")
      (node (ref "D6") (pin "1") (pinfunction "1_1") (pintype "passive"))
      (node (ref "R21") (pin "1") (pinfunction "1_1") (pintype "passive"))
    )
    (net (code "49") (name "Net-(F1-7)") (class "Default")
      (node (ref "F1") (pin "2") (pinfunction "7_2") (pintype "passive"))
      (node (ref "N3") (pin "A4") (pinfunction "VBUS_A4") (pintype "passive"))
      (node (ref "N3") (pin "A9") (pinfunction "VBUS_A9") (pintype "passive"))
    )
    (net (code "50") (name "Net-(F3-6)") (class "Default")
      (node (ref "C19") (pin "1") (pinfunction "1_1") (pintype "passive"))
      (node (ref "F3") (pin "1") (pinfunction "6_1") (pintype "passive"))
      (node (ref "L1") (pin "2") (pintype "passive"))
      (node (ref "U3") (pin "3") (pinfunction "FEEDBACK_3") (pintype "passive"))
    )
    (net (code "51") (name "Net-(F4-6)") (class "Default")
      (node (ref "F4") (pin "1") (pinfunction "6_1") (pintype "passive"))
      (node (ref "N8") (pin "1") (pintype "input"))
    )
    (net (code "52") (name "Net-(N1-Pad2)") (class "Default")
      (node (ref "N1") (pin "2") (pintype "input"))
      (node (ref "R2") (pin "1") (pinfunction "1_1") (pintype "passive"))
    )
    (net (code "53") (name "Net-(Q1-B)") (class "Default")
      (node (ref "Q1") (pin "1") (pinfunction "B_1") (pintype "passive"))
      (node (ref "R12") (pin "2") (pinfunction "2_2") (pintype "passive"))
    )
    (net (code "54") (name "Net-(U1-PD0_OSC_IN)") (class "Default")
      (node (ref "C8") (pin "1") (pinfunction "1_1") (pintype "passive"))
      (node (ref "R6") (pin "1") (pinfunction "1_1") (pintype "passive"))
      (node (ref "U1") (pin "5") (pinfunction "PD0_OSC_IN_5") (pintype "passive"))
      (node (ref "X2") (pin "1") (pinfunction "X1_1") (pintype "passive"))
    )
    (net (code "55") (name "Net-(U1-PD1_OSC_OUT)") (class "Default")
      (node (ref "C11") (pin "1") (pinfunction "1_1") (pintype "passive"))
      (node (ref "R6") (pin "2") (pinfunction "2_2") (pintype "passive"))
      (node (ref "U1") (pin "6") (pinfunction "PD1_OSC_OUT_6") (pintype "passive"))
      (node (ref "X2") (pin "3") (pinfunction "X2_3") (pintype "passive"))
    )
    (net (code "56") (name "Net-(U1-VDD_A(+))") (class "Default")
      (node (ref "BB1") (pin "2") (pintype "passive"))
      (node (ref "C1") (pin "1") (pinfunction "1_1") (pintype "passive"))
      (node (ref "C2") (pin "2") (pinfunction "2_2") (pintype "passive"))
      (node (ref "U1") (pin "9") (pinfunction "VDD_A(+)_9") (pintype "passive"))
    )
    (net (code "57") (name "Net-(U2-A)") (class "Default")
      (node (ref "R17") (pin "1") (pinfunction "1_1") (pintype "passive"))
      (node (ref "U2") (pin "6") (pinfunction "A_6") (pintype "passive"))
    )
    (net (code "58") (name "Net-(U2-B)") (class "Default")
      (node (ref "R15") (pin "1") (pinfunction "1_1") (pintype "passive"))
      (node (ref "U2") (pin "7") (pinfunction "B_7") (pintype "passive"))
    )
    (net (code "59") (name "Net-(W1-D_IN)") (class "Default")
      (node (ref "W1") (pin "4") (pinfunction "D_IN_4") (pintype "passive"))
      (node (ref "W4") (pin "2") (pinfunction "D_OUT_2") (pintype "passive"))
    )
    (net (code "60") (name "Net-(W1-D_OUT)") (class "Default")
      (node (ref "W1") (pin "2") (pinfunction "D_OUT_2") (pintype "passive"))
      (node (ref "W3") (pin "4") (pinfunction "D_IN_4") (pintype "passive"))
    )
    (net (code "61") (name "Net-(W2-D_OUT)") (class "Default")
      (node (ref "W2") (pin "2") (pinfunction "D_OUT_2") (pintype "passive"))
      (node (ref "W4") (pin "4") (pinfunction "D_IN_4") (pintype "passive"))
    )
    (net (code "62") (name "unconnected-(N3-CC1-PadA5)") (class "Default")
      (node (ref "N3") (pin "A5") (pinfunction "CC1_A5") (pintype "passive"))
    )
    (net (code "63") (name "unconnected-(N3-CC2-PadB5)") (class "Default")
      (node (ref "N3") (pin "B5") (pinfunction "CC2_B5") (pintype "passive"))
    )
    (net (code "64") (name "unconnected-(N3-SBU1-PadA8)") (class "Default")
      (node (ref "N3") (pin "A8") (pinfunction "SBU1_A8") (pintype "passive"))
    )
    (net (code "65") (name "unconnected-(N3-SBU2-PadB8)") (class "Default")
      (node (ref "N3") (pin "B8") (pinfunction "SBU2_B8") (pintype "passive"))
    )
    (net (code "66") (name "unconnected-(N5-Pad1)") (class "Default")
      (node (ref "N5") (pin "1") (pinfunction "1_1") (pintype "passive"))
    )
    (net (code "67") (name "unconnected-(N5-Pad2)") (class "Default")
      (node (ref "N5") (pin "2") (pinfunction "2_2") (pintype "passive"))
    )
    (net (code "68") (name "unconnected-(N5-Pad3)") (class "Default")
      (node (ref "N5") (pin "3") (pinfunction "3_3") (pintype "passive"))
    )
    (net (code "69") (name "unconnected-(N5-Pad6)") (class "Default")
      (node (ref "N5") (pin "6") (pinfunction "6_6") (pintype "passive"))
    )
    (net (code "70") (name "unconnected-(N6-Pad1)") (class "Default")
      (node (ref "N6") (pin "1") (pinfunction "1_1") (pintype "passive"))
    )
    (net (code "71") (name "unconnected-(N6-Pad2)") (class "Default")
      (node (ref "N6") (pin "2") (pinfunction "2_2") (pintype "passive"))
    )
    (net (code "72") (name "unconnected-(N6-Pad3)") (class "Default")
      (node (ref "N6") (pin "3") (pinfunction "3_3") (pintype "passive"))
    )
    (net (code "73") (name "unconnected-(N6-Pad6)") (class "Default")
      (node (ref "N6") (pin "6") (pinfunction "6_6") (pintype "passive"))
    )
    (net (code "74") (name "unconnected-(U1-PA0_USART2_CTS{slash}ADC12_IN0{slash}TIM2_CH1{slash}ETR-Pad10)") (class "Default")
      (node (ref "U1") (pin "10") (pinfunction "PA0_USART2_CTS/ADC12_IN0/TIM2_CH1/ETR_10") (pintype "passive"))
    )
    (net (code "75") (name "unconnected-(U1-PA8_USART1_CK{slash}TIM1_CH1{slash}MCO-Pad29)") (class "Default")
      (node (ref "U1") (pin "29") (pinfunction "PA8_USART1_CK/TIM1_CH1/MCO_29") (pintype "passive"))
    )
    (net (code "76") (name "unconnected-(U1-PB6_I2C1_SCL{slash}TIM4_CH1{slash}USART1_TX-Pad42)") (class "Default")
      (node (ref "U1") (pin "42") (pinfunction "PB6_I2C1_SCL/TIM4_CH1/USART1_TX_42") (pintype "passive"))
    )
    (net (code "77") (name "unconnected-(U1-PB7_I2C1_SDA{slash}TIM4_CH2{slash}USART1_RX-Pad43)") (class "Default")
      (node (ref "U1") (pin "43") (pinfunction "PB7_I2C1_SDA/TIM4_CH2/USART1_RX_43") (pintype "passive"))
    )
    (net (code "78") (name "unconnected-(U1-PC13-TAMPER-RTC-Pad2)") (class "Default")
      (node (ref "U1") (pin "2") (pinfunction "PC13-TAMPER-RTC_2") (pintype "passive"))
    )
    (net (code "79") (name "unconnected-(U3-~{EN}-Pad4)") (class "Default")
      (node (ref "U3") (pin "4") (pinfunction "~{EN}_4") (pintype "passive"))
    )
    (net (code "80") (name "unconnected-(X2-NC-Pad2)") (class "Default")
      (node (ref "X2") (pin "2") (pinfunction "NC_2") (pintype "passive"))
    )
    (net (code "81") (name "unconnected-(X2-NC-Pad4)") (class "Default")
      (node (ref "X2") (pin "4") (pinfunction "NC_4") (pintype "passive"))
    )
  )
)
